# LeakSensor.net
KiCad netlist of a schematic drawn in EasyEDA Pro
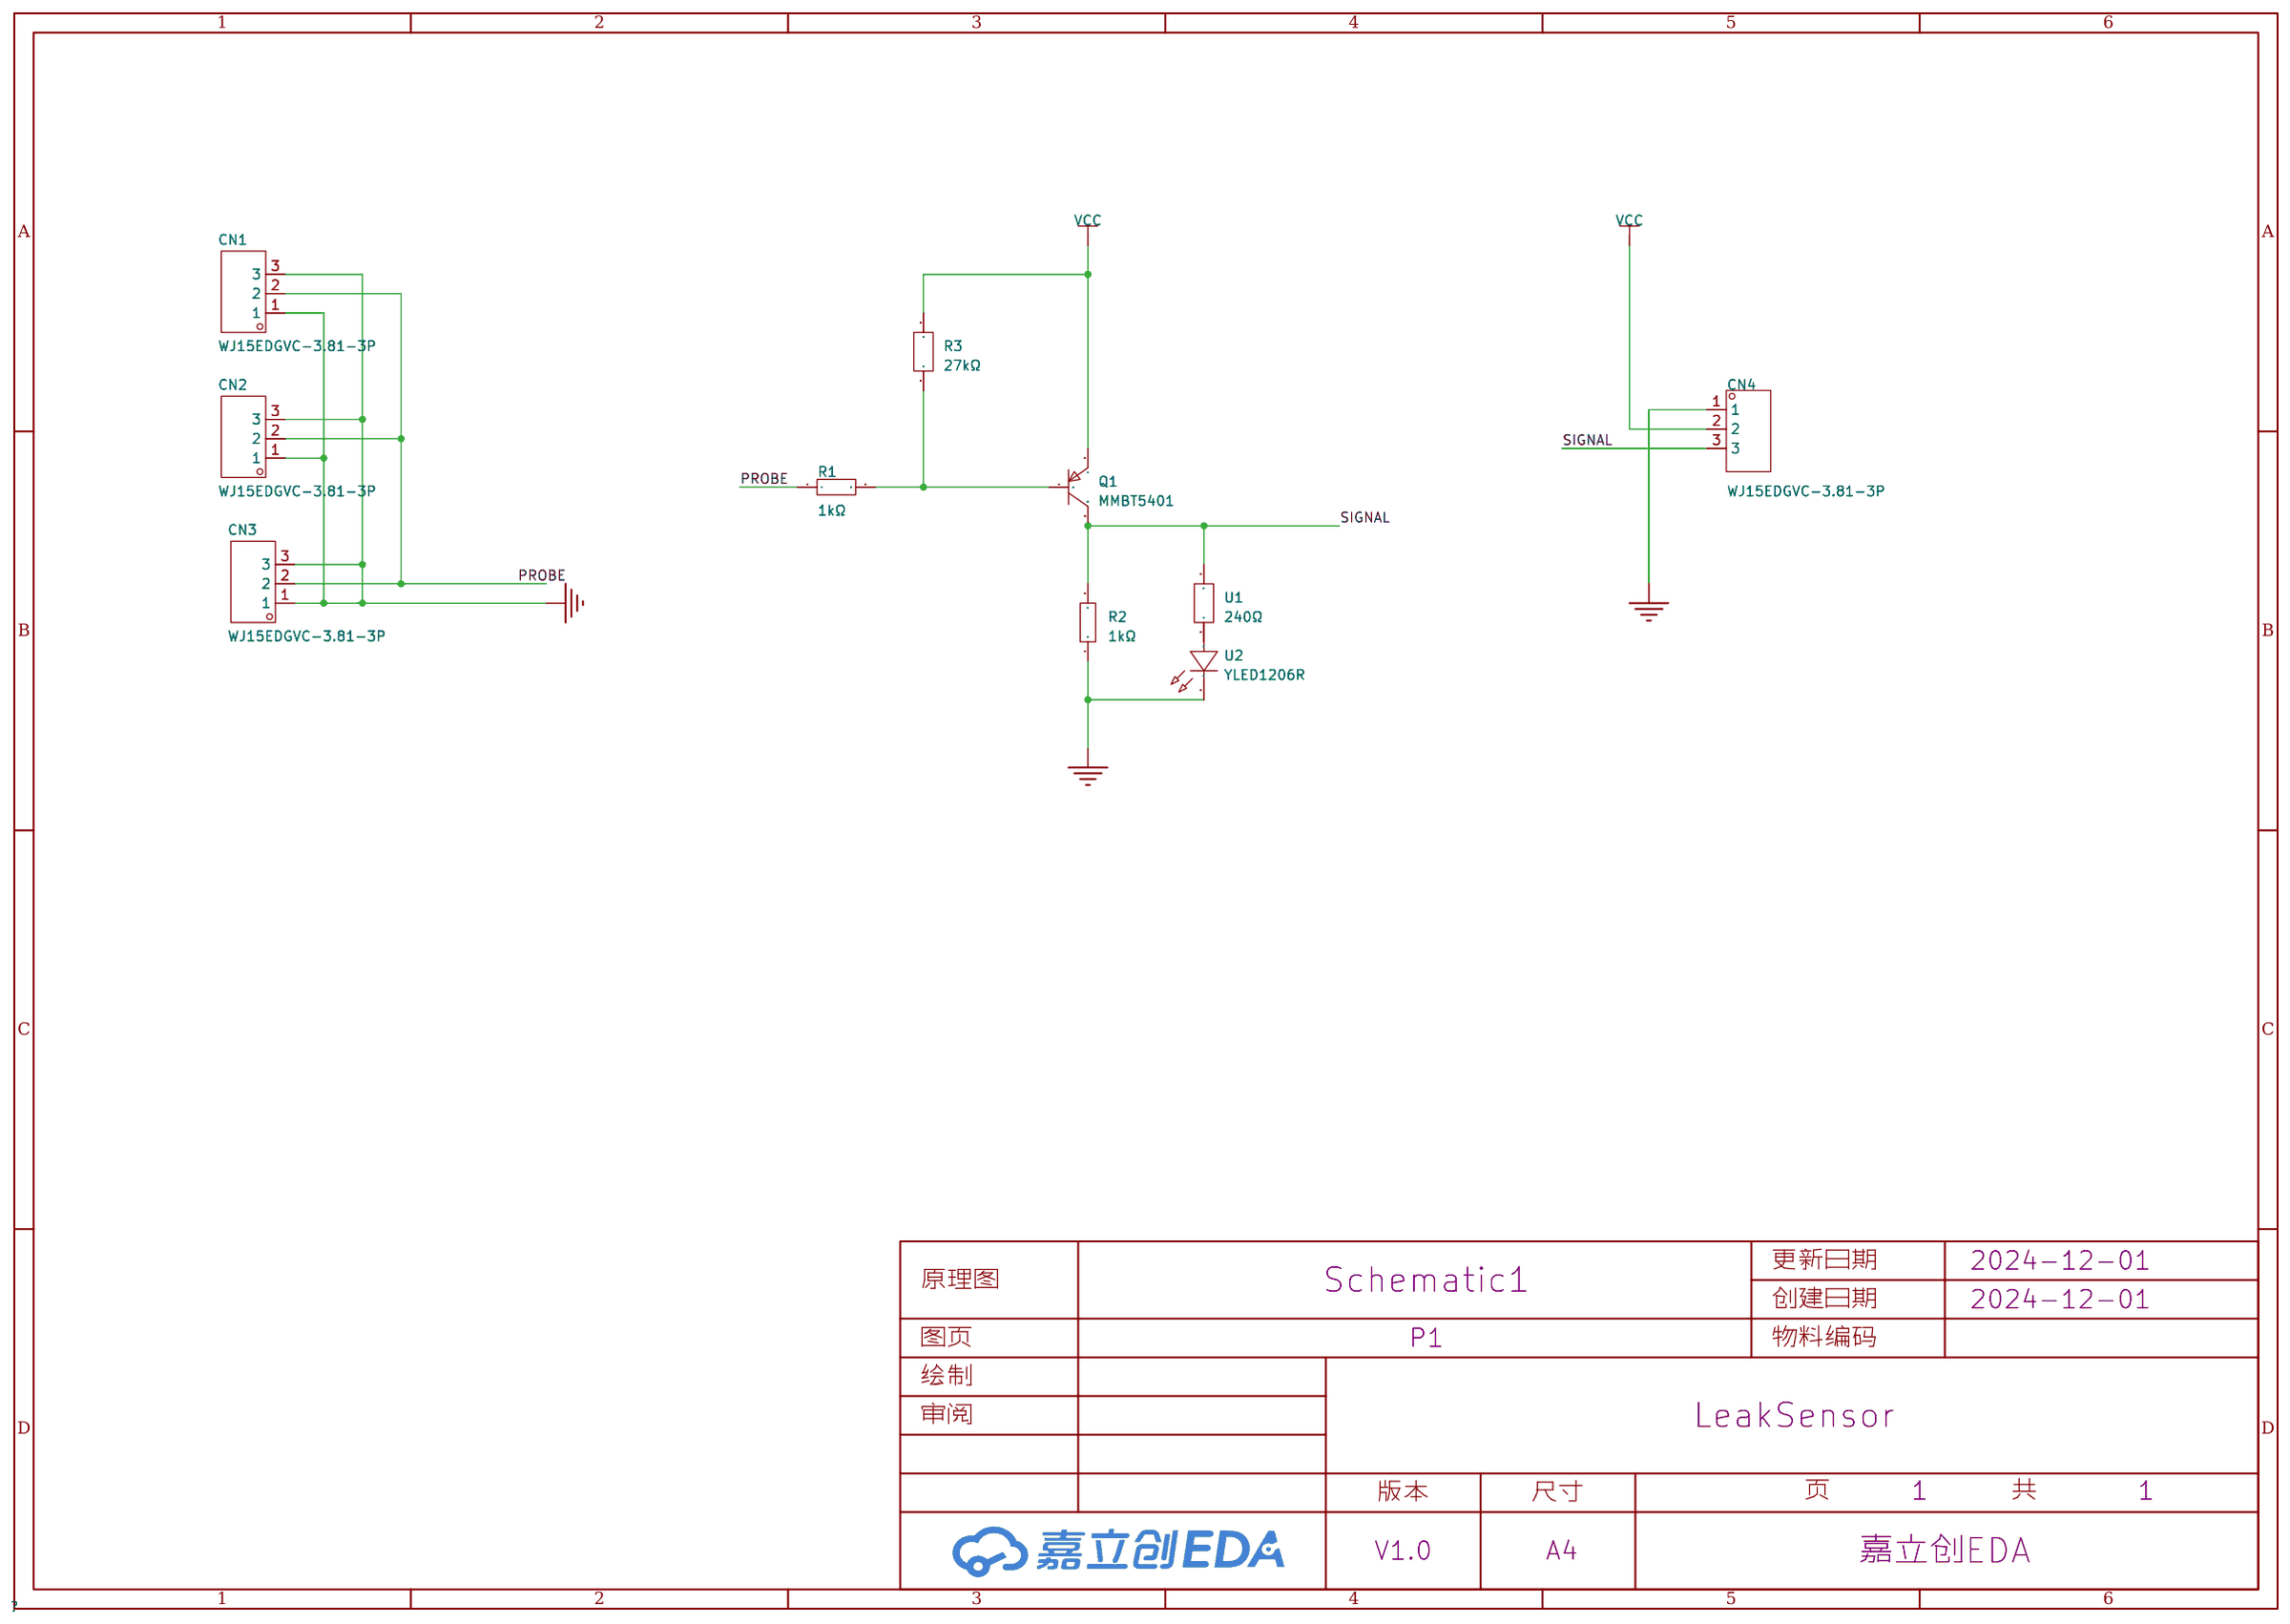
[diagram p0: schematic sheet]

(export (version "E")
  (design (tool "Eeschema 10.0.6"))
  (components
    (comp (ref "CN1")
      (value "WJ15EDGVC-3.81-3P")
      (footprint "easyedapro:CONN-TH_3P-P3.81_WJ15EDGVC-3.81-3P")
      (fields (field (name "Manufacturer") "KANGNEX(康奈克斯电气)"))
      (libsource (lib "easyedapro") (part "WJ15EDGVC-3.81-3P"))
    )
    (comp (ref "CN2")
      (value "WJ15EDGVC-3.81-3P")
      (footprint "easyedapro:CONN-TH_3P-P3.81_WJ15EDGVC-3.81-3P")
      (fields (field (name "Manufacturer") "KANGNEX(康奈克斯电气)"))
      (libsource (lib "easyedapro") (part "WJ15EDGVC-3.81-3P"))
    )
    (comp (ref "CN3")
      (value "WJ15EDGVC-3.81-3P")
      (footprint "easyedapro:CONN-TH_3P-P3.81_WJ15EDGVC-3.81-3P")
      (fields (field (name "Manufacturer") "KANGNEX(康奈克斯电气)"))
      (libsource (lib "easyedapro") (part "WJ15EDGVC-3.81-3P"))
    )
    (comp (ref "CN4")
      (value "WJ15EDGVC-3.81-3P")
      (footprint "easyedapro:CONN-TH_3P-P3.81_WJ15EDGVC-3.81-3P")
      (fields (field (name "Manufacturer") "KANGNEX(康奈克斯电气)"))
      (libsource (lib "easyedapro") (part "WJ15EDGVC-3.81-3P"))
    )
    (comp (ref "Q1")
      (value "MMBT5401")
      (footprint "easyedapro:SOT-23-3_L2.9-W1.3-P1.90-LS2.4-BR")
      (description "晶体管类型:PNP;集电极电流(Ic):600mA;集射极击穿电压(Vceo):160V;功率(Pd):300mW;直流电流增益(hFE@Ic,Vce):100@10mA,5.0V;")
      (fields (field (name "Manufacturer") "宏迦橙"))
      (libsource (lib "easyedapro") (part "MMBT5401_C7420356"))
    )
    (comp (ref "R1")
      (value "1kΩ")
      (footprint "easyedapro:R1206")
      (description "电阻类型:厚膜电阻;阻值:1kΩ;精度:±1%;功率:250mW;最大工作电压:200V;")
      (fields
        (field (name "Manufacturer Part") "1206W4F1001T5E")
        (field (name "Manufacturer") "UNI-ROYAL(厚声)")
      )
      (libsource (lib "easyedapro") (part "1206W4F1001T5E"))
    )
    (comp (ref "R2")
      (value "1kΩ")
      (footprint "easyedapro:R1206")
      (description "电阻类型:厚膜电阻;阻值:1kΩ;精度:±1%;功率:250mW;最大工作电压:200V;")
      (fields
        (field (name "Manufacturer Part") "1206W4F1001T5E")
        (field (name "Manufacturer") "UNI-ROYAL(厚声)")
      )
      (libsource (lib "easyedapro") (part "1206W4F1001T5E"))
    )
    (comp (ref "R3")
      (value "27kΩ")
      (footprint "easyedapro:R2010")
      (description "电阻类型:厚膜电阻;阻值:27kΩ;精度:±1%;功率:750mW;最大工作电压:200V;温度系数:±100ppm/°C;")
      (fields (field (name "Manufacturer Part") "FRC2010F2702TS") (field (name "Manufacturer") "FOJAN(富捷)"))
      (libsource (lib "easyedapro") (part "FRC2010F2702TS"))
    )
    (comp (ref "U1")
      (value "240Ω")
      (footprint "easyedapro:R1206")
      (description "电阻类型:厚膜电阻;阻值:240Ω;精度:±1%;功率:250mW;最大工作电压:200V;温度系数:±100ppm/°C;")
      (fields (field (name "Manufacturer Part") "FRC1206F2400TS") (field (name "Manufacturer") "FOJAN(富捷)"))
      (libsource (lib "easyedapro") (part "FRC1206F2400TS"))
    )
    (comp (ref "U2")
      (value "YLED1206R")
      (footprint "easyedapro:LED1206-FD")
      (description "红色")
      (fields (field (name "Manufacturer") "YONGYUTAI(永裕泰)"))
      (libsource (lib "easyedapro") (part "YLED1206R"))
    )
  )
  (nets
    (net (code "1") (name "/PROBE") (class "Default")
      (node (ref "CN1") (pin "2") (pinfunction "2_2") (pintype "unspecified"))
      (node (ref "CN2") (pin "2") (pinfunction "2_2") (pintype "unspecified"))
      (node (ref "CN3") (pin "2") (pinfunction "2_2") (pintype "unspecified"))
      (node (ref "R1") (pin "1") (pinfunction "1_1") (pintype "input"))
    )
    (net (code "2") (name "/SIGNAL") (class "Default")
      (node (ref "CN4") (pin "3") (pinfunction "3_3") (pintype "unspecified"))
      (node (ref "Q1") (pin "3") (pinfunction "C_3") (pintype "input"))
      (node (ref "R2") (pin "2") (pinfunction "2_2") (pintype "input"))
      (node (ref "U1") (pin "2") (pinfunction "2_2") (pintype "unspecified"))
    )
    (net (code "3") (name "GND") (class "Default")
      (node (ref "CN1") (pin "1") (pinfunction "1_1") (pintype "unspecified"))
      (node (ref "CN1") (pin "3") (pinfunction "3_3") (pintype "unspecified"))
      (node (ref "CN2") (pin "1") (pinfunction "1_1") (pintype "unspecified"))
      (node (ref "CN2") (pin "3") (pinfunction "3_3") (pintype "unspecified"))
      (node (ref "CN3") (pin "1") (pinfunction "1_1") (pintype "unspecified"))
      (node (ref "CN3") (pin "3") (pinfunction "3_3") (pintype "unspecified"))
      (node (ref "CN4") (pin "1") (pinfunction "1_1") (pintype "unspecified"))
      (node (ref "R2") (pin "1") (pinfunction "1_1") (pintype "input"))
      (node (ref "U2") (pin "2") (pinfunction "2_2") (pintype "unspecified"))
    )
    (net (code "4") (name "Net-(Q1-B)") (class "Default")
      (node (ref "Q1") (pin "1") (pinfunction "B_1") (pintype "input"))
      (node (ref "R1") (pin "2") (pinfunction "2_2") (pintype "input"))
      (node (ref "R3") (pin "1") (pinfunction "1_1") (pintype "unspecified"))
    )
    (net (code "5") (name "Net-(U1-Pad1)") (class "Default")
      (node (ref "U1") (pin "1") (pinfunction "1_1") (pintype "unspecified"))
      (node (ref "U2") (pin "1") (pinfunction "1_1") (pintype "unspecified"))
    )
    (net (code "6") (name "VCC") (class "Default")
      (node (ref "CN4") (pin "2") (pinfunction "2_2") (pintype "unspecified"))
      (node (ref "Q1") (pin "2") (pinfunction "E_2") (pintype "input"))
      (node (ref "R3") (pin "2") (pinfunction "2_2") (pintype "unspecified"))
    )
  )
)
